# design.net
KiCad netlist of a schematic drawn in EasyEDA Pro
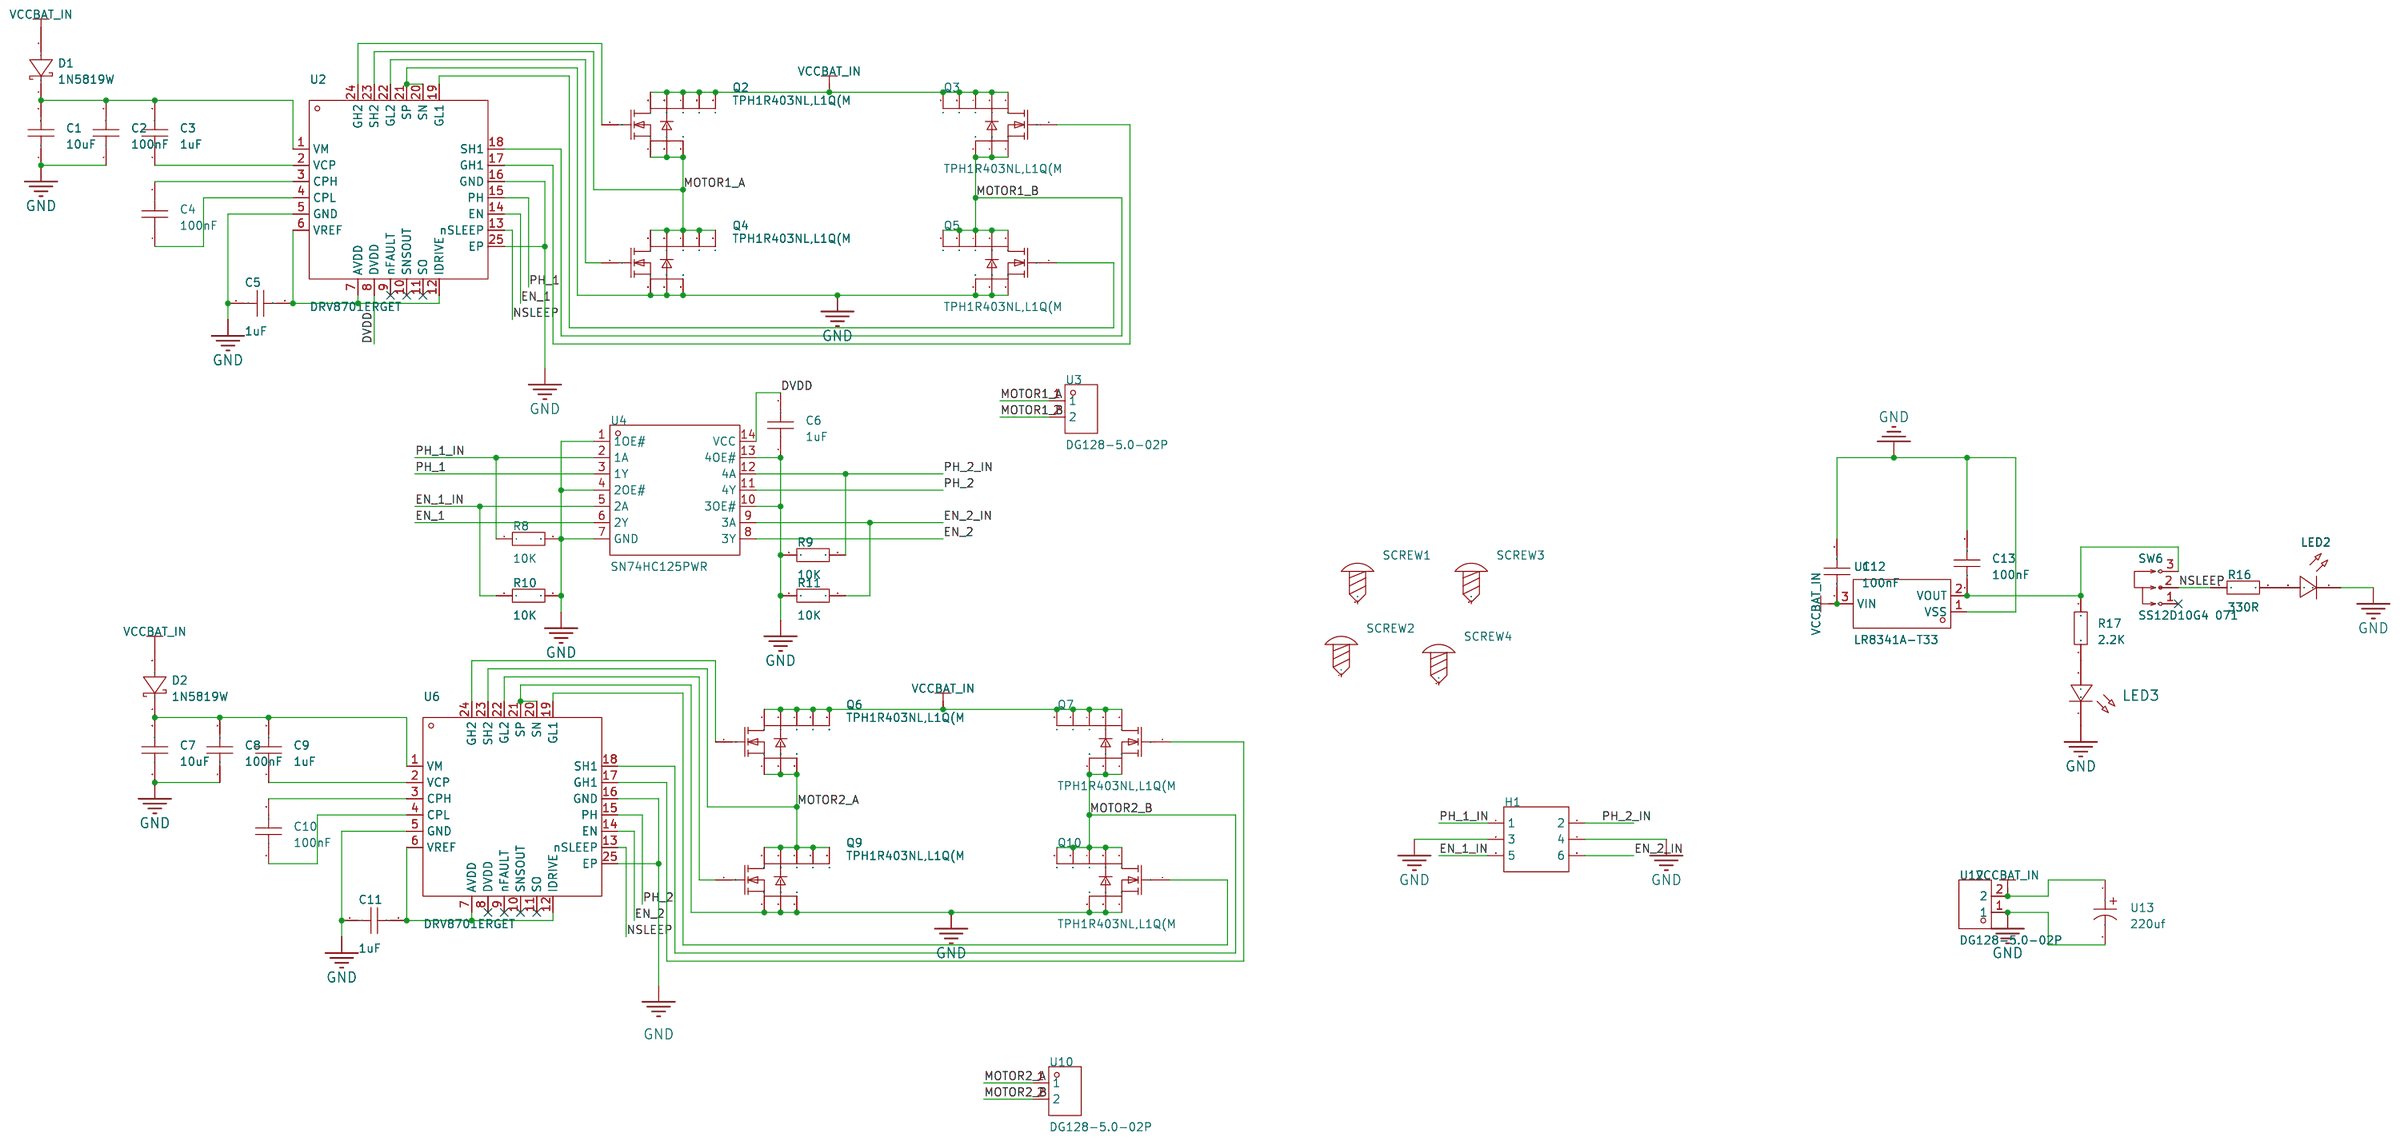
[diagram p0: schematic sheet]

(export (version "E")
  (design (tool "Eeschema 10.0.6"))
  (components
    (comp (ref "C1")
      (value "10uF")
      (footprint "easyedapro:C0603")
      (libsource (lib "easyedapro") (part "CapAcitance"))
    )
    (comp (ref "C2")
      (value "100nF")
      (footprint "easyedapro:C0603")
      (libsource (lib "easyedapro") (part "CapAcitance"))
    )
    (comp (ref "C3")
      (value "1uF")
      (footprint "easyedapro:C0603")
      (libsource (lib "easyedapro") (part "CapAcitance"))
    )
    (comp (ref "C4")
      (value "100nF")
      (footprint "easyedapro:C0603")
      (libsource (lib "easyedapro") (part "CapAcitance"))
    )
    (comp (ref "C5")
      (value "1uF")
      (footprint "easyedapro:C0603")
      (libsource (lib "easyedapro") (part "CapAcitance"))
    )
    (comp (ref "C6")
      (value "1uF")
      (footprint "easyedapro:C0603")
      (libsource (lib "easyedapro") (part "CapAcitance"))
    )
    (comp (ref "C7")
      (value "10uF")
      (footprint "easyedapro:C0603")
      (libsource (lib "easyedapro") (part "CapAcitance"))
    )
    (comp (ref "C8")
      (value "100nF")
      (footprint "easyedapro:C0603")
      (libsource (lib "easyedapro") (part "CapAcitance"))
    )
    (comp (ref "C9")
      (value "1uF")
      (footprint "easyedapro:C0603")
      (libsource (lib "easyedapro") (part "CapAcitance"))
    )
    (comp (ref "C10")
      (value "100nF")
      (footprint "easyedapro:C0603")
      (libsource (lib "easyedapro") (part "CapAcitance"))
    )
    (comp (ref "C11")
      (value "1uF")
      (footprint "easyedapro:C0603")
      (libsource (lib "easyedapro") (part "CapAcitance"))
    )
    (comp (ref "C12")
      (value "100nF")
      (footprint "easyedapro:C0603")
      (libsource (lib "easyedapro") (part "CapAcitance"))
    )
    (comp (ref "C13")
      (value "100nF")
      (footprint "easyedapro:C0603")
      (libsource (lib "easyedapro") (part "CapAcitance"))
    )
    (comp (ref "D1")
      (value "1N5819W")
      (footprint "easyedapro:SOD-123_L2.7-W1.6-LS3.7-RD-1")
      (description "二极管配置:-;正向压降(Vf):900mV@3A;直流反向耐压(Vr):40V;平均整流电流(Io):1A;")
      (fields (field (name "Manufacturer") "TECH PUBLIC(台舟)"))
      (libsource (lib "easyedapro") (part "1N5819W_C2905650"))
    )
    (comp (ref "D2")
      (value "1N5819W")
      (footprint "easyedapro:SOD-123_L2.7-W1.6-LS3.7-RD-1")
      (description "二极管配置:-;正向压降(Vf):900mV@3A;直流反向耐压(Vr):40V;平均整流电流(Io):1A;")
      (fields (field (name "Manufacturer") "TECH PUBLIC(台舟)"))
      (libsource (lib "easyedapro") (part "1N5819W_C2905650"))
    )
    (comp (ref "H1")
      (value "~")
      (footprint "easyedapro:HDR-TH_6P-P2.54-V-F-R2-C3-S2.54")
      (libsource (lib "easyedapro") (part "HDR-F-2.54_2x3"))
    )
    (comp (ref "LED2")
      (value "~")
      (footprint "easyedapro:LED_0603")
      (libsource (lib "easyedapro") (part "LED_G"))
    )
    (comp (ref "LED3")
      (value "~")
      (footprint "easyedapro:LED_0603")
      (libsource (lib "easyedapro") (part "LED_R"))
    )
    (comp (ref "Q2")
      (value "TPH1R403NL,L1Q(M")
      (footprint "easyedapro:DSOP-8_L5.0-W5.0-P1.27-LS6.0-BL-EP")
      (fields (field (name "Manufacturer") "TOSHIBA(东芝)"))
      (libsource (lib "easyedapro") (part "TPH1R403NL,L1Q(M"))
    )
    (comp (ref "Q3")
      (value "TPH1R403NL,L1Q(M")
      (footprint "easyedapro:DSOP-8_L5.0-W5.0-P1.27-LS6.0-BL-EP")
      (fields (field (name "Manufacturer") "TOSHIBA(东芝)"))
      (libsource (lib "easyedapro") (part "TPH1R403NL,L1Q(M"))
    )
    (comp (ref "Q4")
      (value "TPH1R403NL,L1Q(M")
      (footprint "easyedapro:DSOP-8_L5.0-W5.0-P1.27-LS6.0-BL-EP")
      (fields (field (name "Manufacturer") "TOSHIBA(东芝)"))
      (libsource (lib "easyedapro") (part "TPH1R403NL,L1Q(M"))
    )
    (comp (ref "Q5")
      (value "TPH1R403NL,L1Q(M")
      (footprint "easyedapro:DSOP-8_L5.0-W5.0-P1.27-LS6.0-BL-EP")
      (fields (field (name "Manufacturer") "TOSHIBA(东芝)"))
      (libsource (lib "easyedapro") (part "TPH1R403NL,L1Q(M"))
    )
    (comp (ref "Q6")
      (value "TPH1R403NL,L1Q(M")
      (footprint "easyedapro:DSOP-8_L5.0-W5.0-P1.27-LS6.0-BL-EP")
      (fields (field (name "Manufacturer") "TOSHIBA(东芝)"))
      (libsource (lib "easyedapro") (part "TPH1R403NL,L1Q(M"))
    )
    (comp (ref "Q7")
      (value "TPH1R403NL,L1Q(M")
      (footprint "easyedapro:DSOP-8_L5.0-W5.0-P1.27-LS6.0-BL-EP")
      (fields (field (name "Manufacturer") "TOSHIBA(东芝)"))
      (libsource (lib "easyedapro") (part "TPH1R403NL,L1Q(M"))
    )
    (comp (ref "Q9")
      (value "TPH1R403NL,L1Q(M")
      (footprint "easyedapro:DSOP-8_L5.0-W5.0-P1.27-LS6.0-BL-EP")
      (fields (field (name "Manufacturer") "TOSHIBA(东芝)"))
      (libsource (lib "easyedapro") (part "TPH1R403NL,L1Q(M"))
    )
    (comp (ref "Q10")
      (value "TPH1R403NL,L1Q(M")
      (footprint "easyedapro:DSOP-8_L5.0-W5.0-P1.27-LS6.0-BL-EP")
      (fields (field (name "Manufacturer") "TOSHIBA(东芝)"))
      (libsource (lib "easyedapro") (part "TPH1R403NL,L1Q(M"))
    )
    (comp (ref "R8") (value "10K") (footprint "easyedapro:R0603") (libsource (lib "easyedapro") (part "电阻")))
    (comp (ref "R9") (value "10K") (footprint "easyedapro:R0603") (libsource (lib "easyedapro") (part "电阻")))
    (comp (ref "R10") (value "10K") (footprint "easyedapro:R0603") (libsource (lib "easyedapro") (part "电阻")))
    (comp (ref "R11") (value "10K") (footprint "easyedapro:R0603") (libsource (lib "easyedapro") (part "电阻")))
    (comp (ref "R16")
      (value "330R")
      (footprint "easyedapro:R0603")
      (libsource (lib "easyedapro") (part "电阻"))
    )
    (comp (ref "R17")
      (value "2.2K")
      (footprint "easyedapro:R0603")
      (libsource (lib "easyedapro") (part "电阻"))
    )
    (comp (ref "SCREW1")
      (value "~")
      (footprint "easyedapro:M3螺丝")
      (libsource (lib "easyedapro") (part "螺丝孔"))
    )
    (comp (ref "SCREW2")
      (value "~")
      (footprint "easyedapro:M3螺丝")
      (libsource (lib "easyedapro") (part "螺丝孔"))
    )
    (comp (ref "SCREW3")
      (value "~")
      (footprint "easyedapro:M3螺丝")
      (libsource (lib "easyedapro") (part "螺丝孔"))
    )
    (comp (ref "SCREW4")
      (value "~")
      (footprint "easyedapro:M3螺丝")
      (libsource (lib "easyedapro") (part "螺丝孔"))
    )
    (comp (ref "SW6")
      (value "SS12D10G4 071")
      (footprint "easyedapro:SW-TH_SHOU-HAN_SS12D10G4")
      (description "电路结构:单刀双掷;安装方式:直插;开关颜色:-;额定电流(DC):2A;额定电压(DC):125V;额定电流(AC):-;额定电压(AC):-;机械寿命:3千次;")
      (fields (field (name "Manufacturer") "SHOU HAN(首韩)"))
      (libsource (lib "easyedapro") (part "SS12D10G4 071"))
    )
    (comp (ref "U2")
      (value "DRV8701ERGET")
      (footprint "easyedapro:VQFN-24_L4.0-W4.0-P0.50-BL-EP2.5")
      (description "驱动电机类型:有刷直流电机;电源电压:0V~5.5V;输出电流:-;接口:并行;")
      (fields (field (name "Manufacturer") "TI(德州仪器)"))
      (libsource (lib "easyedapro") (part "DRV8701ERGET"))
    )
    (comp (ref "U3")
      (value "DG128-5.0-02P")
      (footprint "easyedapro:DG128-5.0-02P")
      (fields
        (field (name "Manufacturer Part") "DG128-5.0-02P-14-00A(H)")
        (field (name "Manufacturer") "DEGSON（高正/高松）")
      )
      (libsource (lib "easyedapro") (part "DG128-5.0-02P"))
    )
    (comp (ref "U4")
      (value "SN74HC125PWR")
      (footprint "easyedapro:TSSOP-14_L5.0-W4.4-P0.65-LS6.5-BL")
      (description "输入类型:-;电源电压:2V~6V;元件数:4;每个元件位数:1;灌电流(IOL):7.8mA;拉电流(IOH):7.8mA;")
      (fields (field (name "Manufacturer") "TI(德州仪器)"))
      (libsource (lib "easyedapro") (part "SN74HC125PWR"))
    )
    (comp (ref "U6")
      (value "DRV8701ERGET")
      (footprint "easyedapro:VQFN-24_L4.0-W4.0-P0.50-BL-EP2.5")
      (description "驱动电机类型:有刷直流电机;电源电压:0V~5.5V;输出电流:-;接口:并行;")
      (fields (field (name "Manufacturer") "TI(德州仪器)"))
      (libsource (lib "easyedapro") (part "DRV8701ERGET"))
    )
    (comp (ref "U10")
      (value "DG128-5.0-02P")
      (footprint "easyedapro:DG128-5.0-02P")
      (fields
        (field (name "Manufacturer Part") "DG128-5.0-02P-14-00A(H)")
        (field (name "Manufacturer") "DEGSON（高正/高松）")
      )
      (libsource (lib "easyedapro") (part "DG128-5.0-02P"))
    )
    (comp (ref "U11")
      (value "LR8341A-T33")
      (footprint "easyedapro:SOT-23-3L_L2.9-W1.6-P1.90-LS2.8-BL")
      (description "输出类型:固定;最大输入电压:40V;输出电压:3.3V;最大输出电流:100mA;电源纹波抑制比(PSRR):55dB@(1kHz);输出极性:正极;")
      (fields (field (name "Manufacturer") "LR(朗瑞)"))
      (libsource (lib "easyedapro") (part "LR8341A-T33"))
    )
    (comp (ref "U12")
      (value "DG128-5.0-02P")
      (footprint "easyedapro:DG128-5.0-02P")
      (fields
        (field (name "Manufacturer Part") "DG128-5.0-02P-14-00A(H)")
        (field (name "Manufacturer") "DEGSON（高正/高松）")
      )
      (libsource (lib "easyedapro") (part "DG128-5.0-02P"))
    )
    (comp (ref "U13")
      (value "220uf")
      (footprint "easyedapro:CAP-TH_BD6.3-P2.50-D0.5-FD")
      (libsource (lib "easyedapro") (part "电解电容_C9900022333"))
    )
  )
  (nets
    (net (code "1") (name "/DVDD") (class "Default")
      (node (ref "C6") (pin "2") (pinfunction "2_2") (pintype "input"))
      (node (ref "U2") (pin "8") (pinfunction "DVDD_8") (pintype "unspecified"))
      (node (ref "U4") (pin "14") (pinfunction "VCC_14") (pintype "input"))
    )
    (net (code "2") (name "/EN_1") (class "Default")
      (node (ref "U2") (pin "14") (pinfunction "EN_14") (pintype "unspecified"))
      (node (ref "U4") (pin "6") (pinfunction "2Y_6") (pintype "input"))
    )
    (net (code "3") (name "/EN_1_IN") (class "Default")
      (node (ref "H1") (pin "5") (pinfunction "5_5") (pintype "input"))
      (node (ref "R10") (pin "1") (pinfunction "1_1") (pintype "input"))
      (node (ref "U4") (pin "5") (pinfunction "2A_5") (pintype "input"))
    )
    (net (code "4") (name "/EN_2") (class "Default")
      (node (ref "U4") (pin "8") (pinfunction "3Y_8") (pintype "input"))
      (node (ref "U6") (pin "14") (pinfunction "EN_14") (pintype "unspecified"))
    )
    (net (code "5") (name "/EN_2_IN") (class "Default")
      (node (ref "H1") (pin "6") (pinfunction "6_6") (pintype "input"))
      (node (ref "R11") (pin "2") (pinfunction "2_2") (pintype "input"))
      (node (ref "U4") (pin "9") (pinfunction "3A_9") (pintype "input"))
    )
    (net (code "6") (name "/MOTOR1_A") (class "Default")
      (node (ref "Q2") (pin "1") (pinfunction "S_1") (pintype "unspecified"))
      (node (ref "Q2") (pin "2") (pinfunction "S_2") (pintype "unspecified"))
      (node (ref "Q2") (pin "3") (pinfunction "S_3") (pintype "unspecified"))
      (node (ref "Q4") (pin "5") (pinfunction "D_5") (pintype "unspecified"))
      (node (ref "Q4") (pin "6") (pinfunction "D_6") (pintype "unspecified"))
      (node (ref "Q4") (pin "7") (pinfunction "D_7") (pintype "unspecified"))
      (node (ref "Q4") (pin "8") (pinfunction "D_8") (pintype "unspecified"))
      (node (ref "Q4") (pin "9") (pinfunction "D_9") (pintype "unspecified"))
      (node (ref "U2") (pin "23") (pinfunction "SH2_23") (pintype "unspecified"))
      (node (ref "U3") (pin "1") (pinfunction "1_1") (pintype "input"))
    )
    (net (code "7") (name "/MOTOR1_B") (class "Default")
      (node (ref "Q3") (pin "1") (pinfunction "S_1") (pintype "unspecified"))
      (node (ref "Q3") (pin "2") (pinfunction "S_2") (pintype "unspecified"))
      (node (ref "Q3") (pin "3") (pinfunction "S_3") (pintype "unspecified"))
      (node (ref "Q5") (pin "5") (pinfunction "D_5") (pintype "unspecified"))
      (node (ref "Q5") (pin "6") (pinfunction "D_6") (pintype "unspecified"))
      (node (ref "Q5") (pin "7") (pinfunction "D_7") (pintype "unspecified"))
      (node (ref "Q5") (pin "8") (pinfunction "D_8") (pintype "unspecified"))
      (node (ref "Q5") (pin "9") (pinfunction "D_9") (pintype "unspecified"))
      (node (ref "U2") (pin "18") (pinfunction "SH1_18") (pintype "unspecified"))
      (node (ref "U3") (pin "2") (pinfunction "2_2") (pintype "input"))
    )
    (net (code "8") (name "/MOTOR2_A") (class "Default")
      (node (ref "Q6") (pin "1") (pinfunction "S_1") (pintype "unspecified"))
      (node (ref "Q6") (pin "2") (pinfunction "S_2") (pintype "unspecified"))
      (node (ref "Q6") (pin "3") (pinfunction "S_3") (pintype "unspecified"))
      (node (ref "Q9") (pin "5") (pinfunction "D_5") (pintype "unspecified"))
      (node (ref "Q9") (pin "6") (pinfunction "D_6") (pintype "unspecified"))
      (node (ref "Q9") (pin "7") (pinfunction "D_7") (pintype "unspecified"))
      (node (ref "Q9") (pin "8") (pinfunction "D_8") (pintype "unspecified"))
      (node (ref "Q9") (pin "9") (pinfunction "D_9") (pintype "unspecified"))
      (node (ref "U10") (pin "1") (pinfunction "1_1") (pintype "input"))
      (node (ref "U6") (pin "23") (pinfunction "SH2_23") (pintype "unspecified"))
    )
    (net (code "9") (name "/MOTOR2_B") (class "Default")
      (node (ref "Q10") (pin "5") (pinfunction "D_5") (pintype "unspecified"))
      (node (ref "Q10") (pin "6") (pinfunction "D_6") (pintype "unspecified"))
      (node (ref "Q10") (pin "7") (pinfunction "D_7") (pintype "unspecified"))
      (node (ref "Q10") (pin "8") (pinfunction "D_8") (pintype "unspecified"))
      (node (ref "Q10") (pin "9") (pinfunction "D_9") (pintype "unspecified"))
      (node (ref "Q7") (pin "1") (pinfunction "S_1") (pintype "unspecified"))
      (node (ref "Q7") (pin "2") (pinfunction "S_2") (pintype "unspecified"))
      (node (ref "Q7") (pin "3") (pinfunction "S_3") (pintype "unspecified"))
      (node (ref "U10") (pin "2") (pinfunction "2_2") (pintype "input"))
      (node (ref "U6") (pin "18") (pinfunction "SH1_18") (pintype "unspecified"))
    )
    (net (code "10") (name "/NSLEEP") (class "Default")
      (node (ref "R16") (pin "1") (pinfunction "1_1") (pintype "input"))
      (node (ref "SW6") (pin "2") (pinfunction "2_2") (pintype "unspecified"))
      (node (ref "U2") (pin "13") (pinfunction "nSLEEP_13") (pintype "unspecified"))
      (node (ref "U6") (pin "13") (pinfunction "nSLEEP_13") (pintype "unspecified"))
    )
    (net (code "11") (name "/PH_1") (class "Default")
      (node (ref "U2") (pin "15") (pinfunction "PH_15") (pintype "unspecified"))
      (node (ref "U4") (pin "3") (pinfunction "1Y_3") (pintype "input"))
    )
    (net (code "12") (name "/PH_1_IN") (class "Default")
      (node (ref "H1") (pin "1") (pinfunction "1_1") (pintype "input"))
      (node (ref "R8") (pin "1") (pinfunction "1_1") (pintype "input"))
      (node (ref "U4") (pin "2") (pinfunction "1A_2") (pintype "input"))
    )
    (net (code "13") (name "/PH_2") (class "Default")
      (node (ref "U4") (pin "11") (pinfunction "4Y_11") (pintype "input"))
      (node (ref "U6") (pin "15") (pinfunction "PH_15") (pintype "unspecified"))
    )
    (net (code "14") (name "/PH_2_IN") (class "Default")
      (node (ref "H1") (pin "2") (pinfunction "2_2") (pintype "input"))
      (node (ref "R9") (pin "2") (pinfunction "2_2") (pintype "input"))
      (node (ref "U4") (pin "12") (pinfunction "4A_12") (pintype "input"))
    )
    (net (code "15") (name "GND") (class "Default")
      (node (ref "C1") (pin "1") (pinfunction "1_1") (pintype "input"))
      (node (ref "C11") (pin "1") (pinfunction "1_1") (pintype "input"))
      (node (ref "C12") (pin "2") (pinfunction "2_2") (pintype "input"))
      (node (ref "C13") (pin "2") (pinfunction "2_2") (pintype "input"))
      (node (ref "C2") (pin "1") (pinfunction "1_1") (pintype "input"))
      (node (ref "C5") (pin "1") (pinfunction "1_1") (pintype "input"))
      (node (ref "C6") (pin "1") (pinfunction "1_1") (pintype "input"))
      (node (ref "C7") (pin "1") (pinfunction "1_1") (pintype "input"))
      (node (ref "C8") (pin "1") (pinfunction "1_1") (pintype "input"))
      (node (ref "H1") (pin "3") (pinfunction "3_3") (pintype "input"))
      (node (ref "H1") (pin "4") (pinfunction "4_4") (pintype "input"))
      (node (ref "LED2") (pin "1") (pinfunction "C_1") (pintype "input"))
      (node (ref "LED3") (pin "1") (pinfunction "C_1") (pintype "input"))
      (node (ref "Q10") (pin "1") (pinfunction "S_1") (pintype "unspecified"))
      (node (ref "Q10") (pin "2") (pinfunction "S_2") (pintype "unspecified"))
      (node (ref "Q10") (pin "3") (pinfunction "S_3") (pintype "unspecified"))
      (node (ref "Q4") (pin "1") (pinfunction "S_1") (pintype "unspecified"))
      (node (ref "Q4") (pin "2") (pinfunction "S_2") (pintype "unspecified"))
      (node (ref "Q4") (pin "3") (pinfunction "S_3") (pintype "unspecified"))
      (node (ref "Q5") (pin "1") (pinfunction "S_1") (pintype "unspecified"))
      (node (ref "Q5") (pin "2") (pinfunction "S_2") (pintype "unspecified"))
      (node (ref "Q5") (pin "3") (pinfunction "S_3") (pintype "unspecified"))
      (node (ref "Q9") (pin "1") (pinfunction "S_1") (pintype "unspecified"))
      (node (ref "Q9") (pin "2") (pinfunction "S_2") (pintype "unspecified"))
      (node (ref "Q9") (pin "3") (pinfunction "S_3") (pintype "unspecified"))
      (node (ref "R10") (pin "2") (pinfunction "2_2") (pintype "input"))
      (node (ref "R11") (pin "1") (pinfunction "1_1") (pintype "input"))
      (node (ref "R8") (pin "2") (pinfunction "2_2") (pintype "input"))
      (node (ref "R9") (pin "1") (pinfunction "1_1") (pintype "input"))
      (node (ref "U11") (pin "1") (pinfunction "VSS_1") (pintype "unspecified"))
      (node (ref "U12") (pin "1") (pinfunction "1_1") (pintype "input"))
      (node (ref "U13") (pin "2") (pinfunction "2_2") (pintype "input"))
      (node (ref "U2") (pin "16") (pinfunction "GND_16") (pintype "unspecified"))
      (node (ref "U2") (pin "20") (pinfunction "SN_20") (pintype "unspecified"))
      (node (ref "U2") (pin "21") (pinfunction "SP_21") (pintype "unspecified"))
      (node (ref "U2") (pin "25") (pinfunction "EP_25") (pintype "unspecified"))
      (node (ref "U2") (pin "5") (pinfunction "GND_5") (pintype "unspecified"))
      (node (ref "U4") (pin "1") (pinfunction "1OE#_1") (pintype "input"))
      (node (ref "U4") (pin "10") (pinfunction "3OE#_10") (pintype "input"))
      (node (ref "U4") (pin "13") (pinfunction "4OE#_13") (pintype "input"))
      (node (ref "U4") (pin "4") (pinfunction "2OE#_4") (pintype "input"))
      (node (ref "U4") (pin "7") (pinfunction "GND_7") (pintype "input"))
      (node (ref "U6") (pin "16") (pinfunction "GND_16") (pintype "unspecified"))
      (node (ref "U6") (pin "20") (pinfunction "SN_20") (pintype "unspecified"))
      (node (ref "U6") (pin "21") (pinfunction "SP_21") (pintype "unspecified"))
      (node (ref "U6") (pin "25") (pinfunction "EP_25") (pintype "unspecified"))
      (node (ref "U6") (pin "5") (pinfunction "GND_5") (pintype "unspecified"))
    )
    (net (code "16") (name "Net-(D1-K)") (class "Default")
      (node (ref "C1") (pin "2") (pinfunction "2_2") (pintype "input"))
      (node (ref "C2") (pin "2") (pinfunction "2_2") (pintype "input"))
      (node (ref "C3") (pin "2") (pinfunction "2_2") (pintype "input"))
      (node (ref "D1") (pin "1") (pinfunction "K_1") (pintype "input"))
      (node (ref "U2") (pin "1") (pinfunction "VM_1") (pintype "unspecified"))
    )
    (net (code "17") (name "Net-(D2-K)") (class "Default")
      (node (ref "C7") (pin "2") (pinfunction "2_2") (pintype "input"))
      (node (ref "C8") (pin "2") (pinfunction "2_2") (pintype "input"))
      (node (ref "C9") (pin "2") (pinfunction "2_2") (pintype "input"))
      (node (ref "D2") (pin "1") (pinfunction "K_1") (pintype "input"))
      (node (ref "U6") (pin "1") (pinfunction "VM_1") (pintype "unspecified"))
    )
    (net (code "18") (name "Net-(LED2-A)") (class "Default")
      (node (ref "LED2") (pin "2") (pinfunction "A_2") (pintype "input"))
      (node (ref "R16") (pin "2") (pinfunction "2_2") (pintype "input"))
    )
    (net (code "19") (name "Net-(LED3-A)") (class "Default")
      (node (ref "LED3") (pin "2") (pinfunction "A_2") (pintype "input"))
      (node (ref "R17") (pin "1") (pinfunction "1_1") (pintype "input"))
    )
    (net (code "20") (name "Net-(Q2-G)") (class "Default")
      (node (ref "Q2") (pin "4") (pinfunction "G_4") (pintype "unspecified"))
      (node (ref "U2") (pin "24") (pinfunction "GH2_24") (pintype "unspecified"))
    )
    (net (code "21") (name "Net-(Q3-G)") (class "Default")
      (node (ref "Q3") (pin "4") (pinfunction "G_4") (pintype "unspecified"))
      (node (ref "U2") (pin "17") (pinfunction "GH1_17") (pintype "unspecified"))
    )
    (net (code "22") (name "Net-(Q4-G)") (class "Default")
      (node (ref "Q4") (pin "4") (pinfunction "G_4") (pintype "unspecified"))
      (node (ref "U2") (pin "22") (pinfunction "GL2_22") (pintype "unspecified"))
    )
    (net (code "23") (name "Net-(Q5-G)") (class "Default")
      (node (ref "Q5") (pin "4") (pinfunction "G_4") (pintype "unspecified"))
      (node (ref "U2") (pin "19") (pinfunction "GL1_19") (pintype "unspecified"))
    )
    (net (code "24") (name "Net-(Q6-G)") (class "Default")
      (node (ref "Q6") (pin "4") (pinfunction "G_4") (pintype "unspecified"))
      (node (ref "U6") (pin "24") (pinfunction "GH2_24") (pintype "unspecified"))
    )
    (net (code "25") (name "Net-(Q7-G)") (class "Default")
      (node (ref "Q7") (pin "4") (pinfunction "G_4") (pintype "unspecified"))
      (node (ref "U6") (pin "17") (pinfunction "GH1_17") (pintype "unspecified"))
    )
    (net (code "26") (name "Net-(Q9-G)") (class "Default")
      (node (ref "Q9") (pin "4") (pinfunction "G_4") (pintype "unspecified"))
      (node (ref "U6") (pin "22") (pinfunction "GL2_22") (pintype "unspecified"))
    )
    (net (code "27") (name "Net-(Q10-G)") (class "Default")
      (node (ref "Q10") (pin "4") (pinfunction "G_4") (pintype "unspecified"))
      (node (ref "U6") (pin "19") (pinfunction "GL1_19") (pintype "unspecified"))
    )
    (net (code "28") (name "Net-(U2-AVDD)") (class "Default")
      (node (ref "C5") (pin "2") (pinfunction "2_2") (pintype "input"))
      (node (ref "U2") (pin "12") (pinfunction "IDRIVE_12") (pintype "unspecified"))
      (node (ref "U2") (pin "6") (pinfunction "VREF_6") (pintype "unspecified"))
      (node (ref "U2") (pin "7") (pinfunction "AVDD_7") (pintype "unspecified"))
    )
    (net (code "29") (name "Net-(U2-CPH)") (class "Default")
      (node (ref "C4") (pin "2") (pinfunction "2_2") (pintype "input"))
      (node (ref "U2") (pin "3") (pinfunction "CPH_3") (pintype "unspecified"))
    )
    (net (code "30") (name "Net-(U2-CPL)") (class "Default")
      (node (ref "C4") (pin "1") (pinfunction "1_1") (pintype "input"))
      (node (ref "U2") (pin "4") (pinfunction "CPL_4") (pintype "unspecified"))
    )
    (net (code "31") (name "Net-(U2-VCP)") (class "Default")
      (node (ref "C3") (pin "1") (pinfunction "1_1") (pintype "input"))
      (node (ref "U2") (pin "2") (pinfunction "VCP_2") (pintype "unspecified"))
    )
    (net (code "32") (name "Net-(U6-AVDD)") (class "Default")
      (node (ref "C11") (pin "2") (pinfunction "2_2") (pintype "input"))
      (node (ref "U6") (pin "12") (pinfunction "IDRIVE_12") (pintype "unspecified"))
      (node (ref "U6") (pin "6") (pinfunction "VREF_6") (pintype "unspecified"))
      (node (ref "U6") (pin "7") (pinfunction "AVDD_7") (pintype "unspecified"))
    )
    (net (code "33") (name "Net-(U6-CPH)") (class "Default")
      (node (ref "C10") (pin "2") (pinfunction "2_2") (pintype "input"))
      (node (ref "U6") (pin "3") (pinfunction "CPH_3") (pintype "unspecified"))
    )
    (net (code "34") (name "Net-(U6-CPL)") (class "Default")
      (node (ref "C10") (pin "1") (pinfunction "1_1") (pintype "input"))
      (node (ref "U6") (pin "4") (pinfunction "CPL_4") (pintype "unspecified"))
    )
    (net (code "35") (name "Net-(U6-VCP)") (class "Default")
      (node (ref "C9") (pin "1") (pinfunction "1_1") (pintype "input"))
      (node (ref "U6") (pin "2") (pinfunction "VCP_2") (pintype "unspecified"))
    )
    (net (code "36") (name "Net-(U11-VOUT)") (class "Default")
      (node (ref "C13") (pin "1") (pinfunction "1_1") (pintype "input"))
      (node (ref "R17") (pin "2") (pinfunction "2_2") (pintype "input"))
      (node (ref "SW6") (pin "3") (pinfunction "3_3") (pintype "unspecified"))
      (node (ref "U11") (pin "2") (pinfunction "VOUT_2") (pintype "unspecified"))
    )
    (net (code "37") (name "VCCBAT_IN") (class "Default")
      (node (ref "C12") (pin "1") (pinfunction "1_1") (pintype "input"))
      (node (ref "D1") (pin "2") (pinfunction "A_2") (pintype "input"))
      (node (ref "D2") (pin "2") (pinfunction "A_2") (pintype "input"))
      (node (ref "Q2") (pin "5") (pinfunction "D_5") (pintype "unspecified"))
      (node (ref "Q2") (pin "6") (pinfunction "D_6") (pintype "unspecified"))
      (node (ref "Q2") (pin "7") (pinfunction "D_7") (pintype "unspecified"))
      (node (ref "Q2") (pin "8") (pinfunction "D_8") (pintype "unspecified"))
      (node (ref "Q2") (pin "9") (pinfunction "D_9") (pintype "unspecified"))
      (node (ref "Q3") (pin "5") (pinfunction "D_5") (pintype "unspecified"))
      (node (ref "Q3") (pin "6") (pinfunction "D_6") (pintype "unspecified"))
      (node (ref "Q3") (pin "7") (pinfunction "D_7") (pintype "unspecified"))
      (node (ref "Q3") (pin "8") (pinfunction "D_8") (pintype "unspecified"))
      (node (ref "Q3") (pin "9") (pinfunction "D_9") (pintype "unspecified"))
      (node (ref "Q6") (pin "5") (pinfunction "D_5") (pintype "unspecified"))
      (node (ref "Q6") (pin "6") (pinfunction "D_6") (pintype "unspecified"))
      (node (ref "Q6") (pin "7") (pinfunction "D_7") (pintype "unspecified"))
      (node (ref "Q6") (pin "8") (pinfunction "D_8") (pintype "unspecified"))
      (node (ref "Q6") (pin "9") (pinfunction "D_9") (pintype "unspecified"))
      (node (ref "Q7") (pin "5") (pinfunction "D_5") (pintype "unspecified"))
      (node (ref "Q7") (pin "6") (pinfunction "D_6") (pintype "unspecified"))
      (node (ref "Q7") (pin "7") (pinfunction "D_7") (pintype "unspecified"))
      (node (ref "Q7") (pin "8") (pinfunction "D_8") (pintype "unspecified"))
      (node (ref "Q7") (pin "9") (pinfunction "D_9") (pintype "unspecified"))
      (node (ref "U11") (pin "3") (pinfunction "VIN_3") (pintype "unspecified"))
      (node (ref "U12") (pin "2") (pinfunction "2_2") (pintype "input"))
      (node (ref "U13") (pin "1") (pinfunction "1_1") (pintype "input"))
    )
    (net (code "38") (name "unconnected-(SCREW1-Pad1)") (class "Default")
      (node (ref "SCREW1") (pin "1") (pinfunction "1_1") (pintype "input"))
    )
    (net (code "39") (name "unconnected-(SCREW2-Pad1)") (class "Default")
      (node (ref "SCREW2") (pin "1") (pinfunction "1_1") (pintype "input"))
    )
    (net (code "40") (name "unconnected-(SCREW3-Pad1)") (class "Default")
      (node (ref "SCREW3") (pin "1") (pinfunction "1_1") (pintype "input"))
    )
    (net (code "41") (name "unconnected-(SCREW4-Pad1)") (class "Default")
      (node (ref "SCREW4") (pin "1") (pinfunction "1_1") (pintype "input"))
    )
    (net (code "42") (name "unconnected-(SW6-Pad1)") (class "Default")
      (node (ref "SW6") (pin "1") (pinfunction "1_1") (pintype "unspecified+no_connect"))
    )
    (net (code "43") (name "unconnected-(U2-SNSOUT-Pad10)") (class "Default")
      (node (ref "U2") (pin "10") (pinfunction "SNSOUT_10") (pintype "unspecified+no_connect"))
    )
    (net (code "44") (name "unconnected-(U2-SO-Pad11)") (class "Default")
      (node (ref "U2") (pin "11") (pinfunction "SO_11") (pintype "unspecified+no_connect"))
    )
    (net (code "45") (name "unconnected-(U2-nFAULT-Pad9)") (class "Default")
      (node (ref "U2") (pin "9") (pinfunction "nFAULT_9") (pintype "unspecified+no_connect"))
    )
    (net (code "46") (name "unconnected-(U6-DVDD-Pad8)") (class "Default")
      (node (ref "U6") (pin "8") (pinfunction "DVDD_8") (pintype "unspecified+no_connect"))
    )
    (net (code "47") (name "unconnected-(U6-SNSOUT-Pad10)") (class "Default")
      (node (ref "U6") (pin "10") (pinfunction "SNSOUT_10") (pintype "unspecified+no_connect"))
    )
    (net (code "48") (name "unconnected-(U6-SO-Pad11)") (class "Default")
      (node (ref "U6") (pin "11") (pinfunction "SO_11") (pintype "unspecified+no_connect"))
    )
    (net (code "49") (name "unconnected-(U6-nFAULT-Pad9)") (class "Default")
      (node (ref "U6") (pin "9") (pinfunction "nFAULT_9") (pintype "unspecified+no_connect"))
    )
  )
)
